# Sensors.net
KiCad netlist of a schematic drawn in Altium Designer
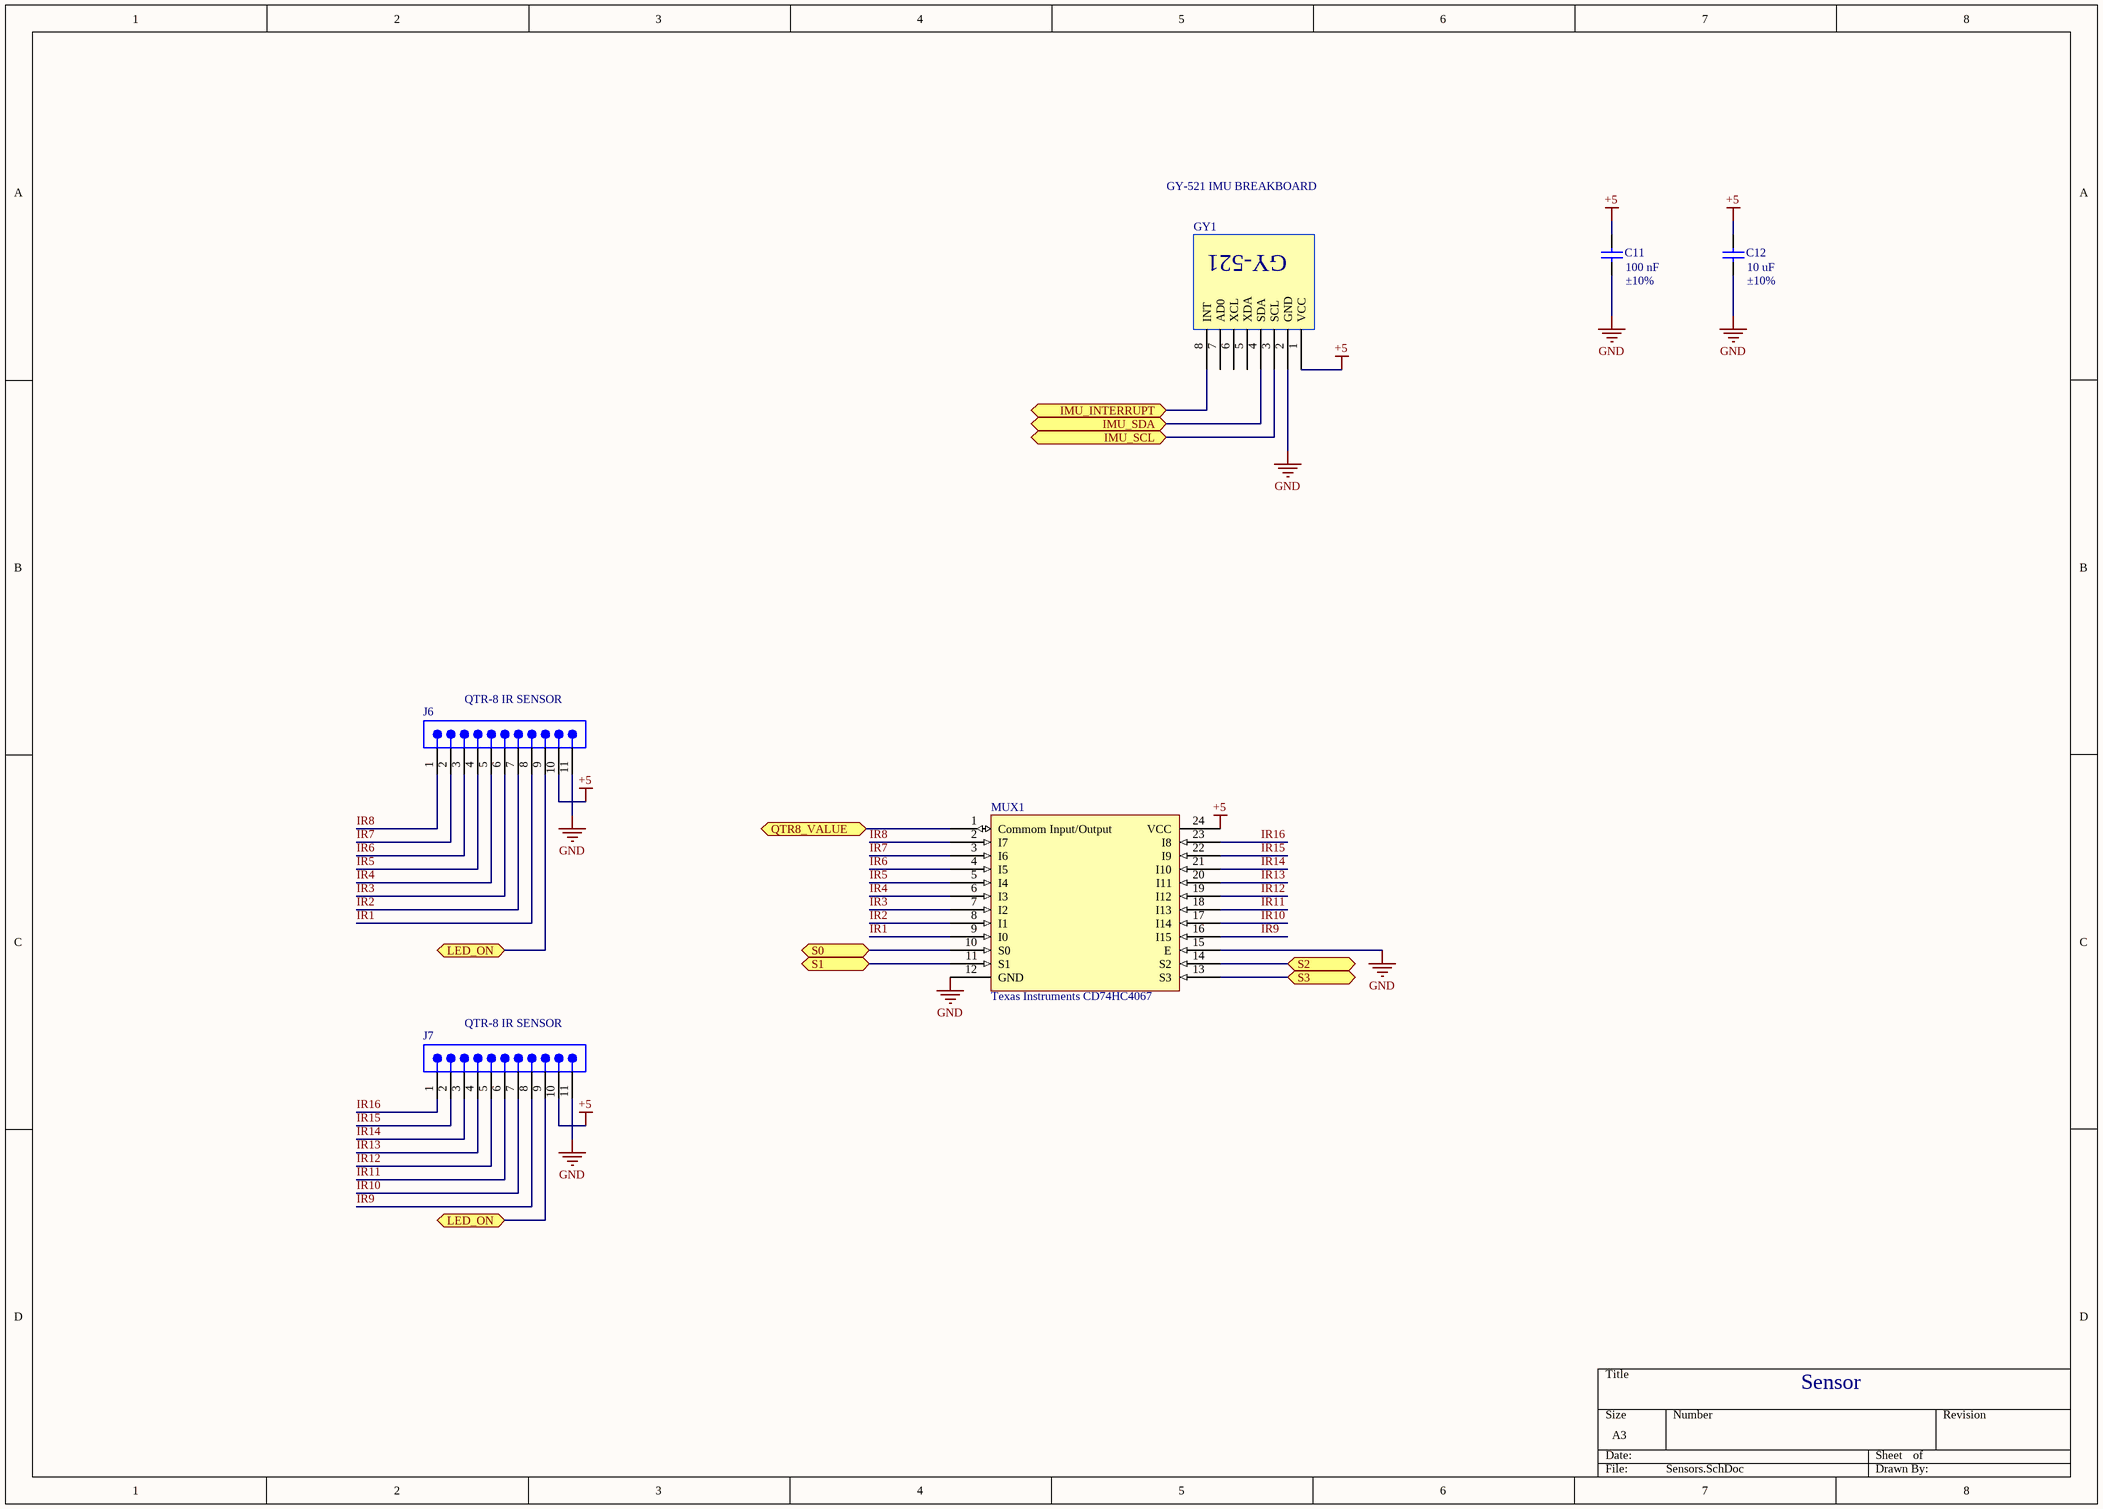
[diagram p0: Sensors.SchDoc]

(export (version "E")
  (design (tool "Eeschema 10.0.6"))
  (components
    (comp (ref "C11")
      (value "Taiyo Yuden LMK212BJ106KG-T")
      (footprint "PCB-i747o4qnz4fc2aqkwc14-1")
      (description "Cap Ceramic 10uF 10V X5R 10% SMD 0805 85?C T/R")
      (fields
        (field (name "MANUFACTURER PART NUMBER") "LMK212BJ106KG-T")
        (field (name "CAPACITANCE") "100 nF")
        (field (name "CAPACITANCE TOLERANCE") "±10%")
      )
      (libsource (lib "CommunityVault") (part "CMP-6ecba7c24c09b10c-2"))
    )
    (comp (ref "C12")
      (value "Taiyo Yuden LMK212BJ106KG-T")
      (footprint "PCB-i747o4qnz4fc2aqkwc14-1")
      (description "Cap Ceramic 10uF 10V X5R 10% SMD 0805 85?C T/R")
      (fields
        (field (name "MANUFACTURER PART NUMBER") "LMK212BJ106KG-T")
        (field (name "CAPACITANCE") "10 uF")
        (field (name "CAPACITANCE TOLERANCE") "±10%")
      )
      (libsource (lib "CommunityVault") (part "CMP-6ecba7c24c09b10c-2"))
    )
    (comp (ref "GY1")
      (value "GY-521 MPU-6050 IMU")
      (footprint "PCBComponent_1")
      (description "3-axis gyroscope, 3-axis accelerometer breakout board")
      (fields (field (name "MANUFACTURER PART NUMBER") "MPU-6050"))
      (libsource (lib "CommunityVault") (part "SYM-29a8e18bafc8f66f-1"))
    )
    (comp (ref "J6")
      (value "Samtec TSW-111-05-G-S")
      (footprint "1X11")
      (description "CONN HEADER 11POS .100\" SGL GOLD")
      (libsource (lib "CommunityVault") (part "CMP-3970764-2"))
    )
    (comp (ref "J7")
      (value "Samtec TSW-111-05-G-S")
      (footprint "1X11")
      (description "CONN HEADER 11POS .100\" SGL GOLD")
      (libsource (lib "CommunityVault") (part "CMP-3970764-2"))
    )
    (comp (ref "MUX1")
      (value "Texas Instruments CD74HC4067")
      (footprint "PCBComponent_1 - duplicate")
      (description "High Speed CMOS 16-Channel Analog Multiplexer/Demultiplexer 24-SSOP -55 to 125")
      (fields (field (name "MANUFACTURER PART NUMBER") "CD74HC4067SM96"))
      (libsource (lib "CommunityVault") (part "CMP-106ed96303d9cfa9-6"))
    )
  )
  (nets
    (net (code "1") (name "+5") (class "Default")
      (node (ref "C11") (pin "2") (pinfunction "2_2") (pintype "passive"))
      (node (ref "C12") (pin "2") (pinfunction "2_2") (pintype "passive"))
      (node (ref "GY1") (pin "1") (pinfunction "VCC_1") (pintype "power_in"))
      (node (ref "J6") (pin "10") (pinfunction "10_10") (pintype "passive"))
      (node (ref "J7") (pin "10") (pinfunction "10_10") (pintype "passive"))
      (node (ref "MUX1") (pin "24") (pinfunction "VCC_24") (pintype "power_in"))
    )
    (net (code "2") (name "/IMU_INTERRUPT") (class "Default")
      (node (ref "GY1") (pin "8") (pinfunction "INT_8") (pintype "passive"))
    )
    (net (code "3") (name "/IMU_SCL") (class "Default")
      (node (ref "GY1") (pin "3") (pinfunction "SCL_3") (pintype "passive"))
    )
    (net (code "4") (name "/IMU_SDA") (class "Default")
      (node (ref "GY1") (pin "4") (pinfunction "SDA_4") (pintype "passive"))
    )
    (net (code "5") (name "/IR1") (class "Default")
      (node (ref "J6") (pin "8") (pinfunction "8_8") (pintype "passive"))
      (node (ref "MUX1") (pin "9") (pinfunction "I0_9") (pintype "input"))
    )
    (net (code "6") (name "/IR2") (class "Default")
      (node (ref "J6") (pin "7") (pinfunction "7_7") (pintype "passive"))
      (node (ref "MUX1") (pin "8") (pinfunction "I1_8") (pintype "input"))
    )
    (net (code "7") (name "/IR3") (class "Default")
      (node (ref "J6") (pin "6") (pinfunction "6_6") (pintype "passive"))
      (node (ref "MUX1") (pin "7") (pinfunction "I2_7") (pintype "input"))
    )
    (net (code "8") (name "/IR4") (class "Default")
      (node (ref "J6") (pin "5") (pinfunction "5_5") (pintype "passive"))
      (node (ref "MUX1") (pin "6") (pinfunction "I3_6") (pintype "input"))
    )
    (net (code "9") (name "/IR5") (class "Default")
      (node (ref "J6") (pin "4") (pinfunction "4_4") (pintype "passive"))
      (node (ref "MUX1") (pin "5") (pinfunction "I4_5") (pintype "input"))
    )
    (net (code "10") (name "/IR6") (class "Default")
      (node (ref "J6") (pin "3") (pinfunction "3_3") (pintype "passive"))
      (node (ref "MUX1") (pin "4") (pinfunction "I5_4") (pintype "input"))
    )
    (net (code "11") (name "/IR7") (class "Default")
      (node (ref "J6") (pin "2") (pinfunction "2_2") (pintype "passive"))
      (node (ref "MUX1") (pin "3") (pinfunction "I6_3") (pintype "input"))
    )
    (net (code "12") (name "/IR8") (class "Default")
      (node (ref "J6") (pin "1") (pinfunction "1_1") (pintype "passive"))
      (node (ref "MUX1") (pin "2") (pinfunction "I7_2") (pintype "input"))
    )
    (net (code "13") (name "/IR9") (class "Default")
      (node (ref "J7") (pin "8") (pinfunction "8_8") (pintype "passive"))
      (node (ref "MUX1") (pin "16") (pinfunction "I15_16") (pintype "input"))
    )
    (net (code "14") (name "/IR10") (class "Default")
      (node (ref "J7") (pin "7") (pinfunction "7_7") (pintype "passive"))
      (node (ref "MUX1") (pin "17") (pinfunction "I14_17") (pintype "input"))
    )
    (net (code "15") (name "/IR11") (class "Default")
      (node (ref "J7") (pin "6") (pinfunction "6_6") (pintype "passive"))
      (node (ref "MUX1") (pin "18") (pinfunction "I13_18") (pintype "input"))
    )
    (net (code "16") (name "/IR12") (class "Default")
      (node (ref "J7") (pin "5") (pinfunction "5_5") (pintype "passive"))
      (node (ref "MUX1") (pin "19") (pinfunction "I12_19") (pintype "input"))
    )
    (net (code "17") (name "/IR13") (class "Default")
      (node (ref "J7") (pin "4") (pinfunction "4_4") (pintype "passive"))
      (node (ref "MUX1") (pin "20") (pinfunction "I11_20") (pintype "input"))
    )
    (net (code "18") (name "/IR14") (class "Default")
      (node (ref "J7") (pin "3") (pinfunction "3_3") (pintype "passive"))
      (node (ref "MUX1") (pin "21") (pinfunction "I10_21") (pintype "input"))
    )
    (net (code "19") (name "/IR15") (class "Default")
      (node (ref "J7") (pin "2") (pinfunction "2_2") (pintype "passive"))
      (node (ref "MUX1") (pin "22") (pinfunction "I9_22") (pintype "input"))
    )
    (net (code "20") (name "/IR16") (class "Default")
      (node (ref "J7") (pin "1") (pinfunction "1_1") (pintype "passive"))
      (node (ref "MUX1") (pin "23") (pinfunction "I8_23") (pintype "input"))
    )
    (net (code "21") (name "/LED_ON") (class "Default")
      (node (ref "J6") (pin "9") (pinfunction "9_9") (pintype "passive"))
      (node (ref "J7") (pin "9") (pinfunction "9_9") (pintype "passive"))
    )
    (net (code "22") (name "/QTR8_VALUE") (class "Default")
      (node (ref "MUX1") (pin "1") (pinfunction "Commom_Input/Output_1") (pintype "bidirectional"))
    )
    (net (code "23") (name "/S0") (class "Default")
      (node (ref "MUX1") (pin "10") (pinfunction "S0_10") (pintype "input"))
    )
    (net (code "24") (name "/S1") (class "Default")
      (node (ref "MUX1") (pin "11") (pinfunction "S1_11") (pintype "input"))
    )
    (net (code "25") (name "/S2") (class "Default")
      (node (ref "MUX1") (pin "14") (pinfunction "S2_14") (pintype "input"))
    )
    (net (code "26") (name "/S3") (class "Default")
      (node (ref "MUX1") (pin "13") (pinfunction "S3_13") (pintype "input"))
    )
    (net (code "27") (name "GND") (class "Default")
      (node (ref "C11") (pin "1") (pinfunction "1_1") (pintype "passive"))
      (node (ref "C12") (pin "1") (pinfunction "1_1") (pintype "passive"))
      (node (ref "GY1") (pin "2") (pinfunction "GND_2") (pintype "power_in"))
      (node (ref "J6") (pin "11") (pinfunction "11_11") (pintype "passive"))
      (node (ref "J7") (pin "11") (pinfunction "11_11") (pintype "passive"))
      (node (ref "MUX1") (pin "12") (pinfunction "GND_12") (pintype "power_in"))
      (node (ref "MUX1") (pin "15") (pinfunction "E_15") (pintype "input"))
    )
    (net (code "28") (name "unconnected-(GY1-AD0-Pad7)") (class "Default")
      (node (ref "GY1") (pin "7") (pinfunction "AD0_7") (pintype "passive"))
    )
    (net (code "29") (name "unconnected-(GY1-XCL-Pad6)") (class "Default")
      (node (ref "GY1") (pin "6") (pinfunction "XCL_6") (pintype "passive"))
    )
    (net (code "30") (name "unconnected-(GY1-XDA-Pad5)") (class "Default")
      (node (ref "GY1") (pin "5") (pinfunction "XDA_5") (pintype "passive"))
    )
  )
)
